# BatteryCharger.net
KiCad netlist of a schematic drawn in Altium Designer
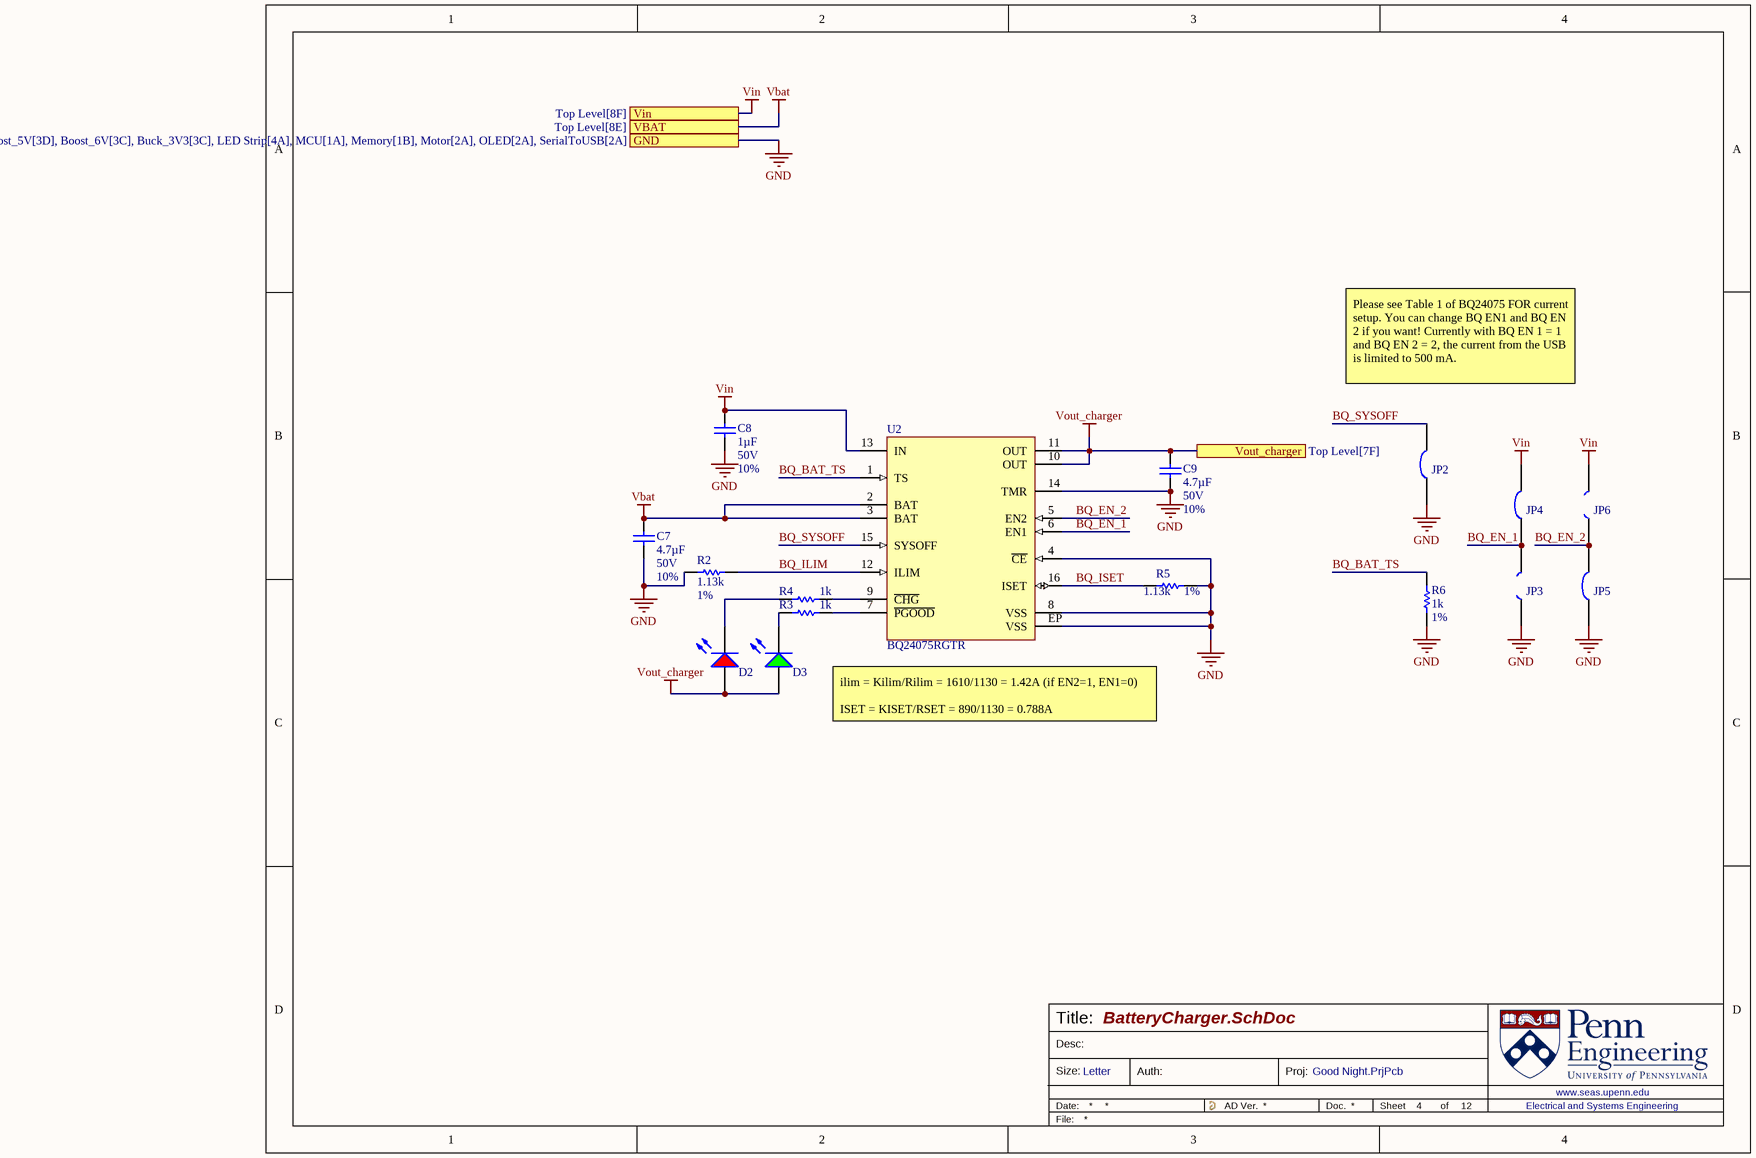
[diagram p0: BatteryCharger.SchDoc]

(export (version "E")
  (design (tool "Eeschema 10.0.6"))
  (components
    (comp (ref "C7")
      (value "4.7µF")
      (footprint "0805_CAP")
      (description "Capacitor Surface Mount 0805 Footprint 4.7UF 50V 10% Tolerance Ceramic X5R")
      (fields
        (field (name "VOLTAGE") "50V")
        (field (name "TOLERANCE") "10%")
        (field (name "Comment") "CAP 0805 4.7UF 50V 10% X5R")
      )
      (libsource (lib "University of Pennsylvania (ESE)") (part "cap"))
    )
    (comp (ref "C8")
      (value "1µF")
      (footprint "0603_CAP")
      (description "Capacitor Surface Mount 0603 Footprint 1UF 50V 10% Tolerance Ceramic X7R")
      (fields
        (field (name "VOLTAGE") "50V")
        (field (name "MANUFACTURER") "Various")
        (field (name "TOLERANCE") "10%")
        (field (name "Comment") "CAP 0603 1UF 50V 10% X7R")
      )
      (libsource (lib "University of Pennsylvania (ESE)") (part "cap"))
    )
    (comp (ref "C9")
      (value "4.7µF")
      (footprint "0805_CAP")
      (description "Capacitor Surface Mount 0805 Footprint 4.7UF 50V 10% Tolerance Ceramic X5R")
      (fields
        (field (name "VOLTAGE") "50V")
        (field (name "TOLERANCE") "10%")
        (field (name "Comment") "CAP 0805 4.7UF 50V 10% X5R")
      )
      (libsource (lib "University of Pennsylvania (ESE)") (part "cap"))
    )
    (comp (ref "D2")
      (value "LSM0805412V")
      (footprint "LED_0805_RED")
      (description "Single Color LED, RED, 0805")
      (libsource (lib "University of Pennsylvania (ESE)") (part "LED-RED-AK-2"))
    )
    (comp (ref "D3")
      (value "LSM0805452V")
      (footprint "LED_0805")
      (description "Single Color LED, Green, 0805")
      (libsource (lib "University of Pennsylvania (ESE)") (part "LED-GREEN-AK-2"))
    )
    (comp (ref "JP2")
      (value "0603 link")
      (footprint "0603_JP_RES")
      (description "0O link, SMD, 0603, Solder Bridge Option")
      (fields (field (name "MANUFACTURER") "Generic") (field (name "SOURCE") "Shunts and Jumpers.SchLib"))
      (libsource (lib "University of Pennsylvania (ESE)") (part "CMP-ROOT-0007-1"))
    )
    (comp (ref "JP3")
      (value "0603 link (Open)")
      (footprint "0603_JP_Open")
      (description "0O link, Solder Bridge/SMD, Open")
      (fields (field (name "SOURCE") "Shunts and Jumpers.SchLib"))
      (libsource (lib "University of Pennsylvania (ESE)") (part "CMP-ROOT-0012-1"))
    )
    (comp (ref "JP4")
      (value "0603 link")
      (footprint "0603_JP_RES")
      (description "0O link, SMD, 0603, Solder Bridge Option")
      (fields (field (name "MANUFACTURER") "Generic") (field (name "SOURCE") "Shunts and Jumpers.SchLib"))
      (libsource (lib "University of Pennsylvania (ESE)") (part "CMP-ROOT-0007-1"))
    )
    (comp (ref "JP5")
      (value "0603 link")
      (footprint "0603_JP_RES")
      (description "0O link, SMD, 0603, Solder Bridge Option")
      (fields (field (name "MANUFACTURER") "Generic") (field (name "SOURCE") "Shunts and Jumpers.SchLib"))
      (libsource (lib "") (part "CMP-ROOT-0007-1_1"))
    )
    (comp (ref "JP6")
      (value "0603 link (Open)")
      (footprint "0603_JP_Open")
      (description "0O link, Solder Bridge/SMD, Open")
      (fields (field (name "SOURCE") "Shunts and Jumpers.SchLib"))
      (libsource (lib "") (part "CMP-ROOT-0012-1_1"))
    )
    (comp (ref "R2")
      (value "1.13k")
      (footprint "0603_RES")
      (description "Resistor Surface Mount, 1.13K Ohms, 0603 Footprint, 1% Tolerance 0.1W")
      (fields
        (field (name "TOLERANCE") "1%")
        (field (name "MANUFACTURER") "Various")
        (field (name "Comment") "RES 0603 1.13K 1%")
      )
      (libsource (lib "University of Pennsylvania (ESE)") (part "res"))
    )
    (comp (ref "R3")
      (value "1k")
      (footprint "0603_RES")
      (description "Resistor Surface Mount, 1K Ohms, 0603 Footprint, 1% Tolerance 0.1W")
      (fields (field (name "JLCPCB PART #") "C21190") (field (name "MANUFACTURER") "Various"))
      (libsource (lib "University of Pennsylvania (ESE)") (part "res"))
    )
    (comp (ref "R4")
      (value "1k")
      (footprint "0603_RES")
      (description "Resistor Surface Mount, 1K Ohms, 0603 Footprint, 1% Tolerance 0.1W")
      (fields (field (name "JLCPCB PART #") "C21190") (field (name "MANUFACTURER") "Various"))
      (libsource (lib "University of Pennsylvania (ESE)") (part "res"))
    )
    (comp (ref "R5")
      (value "1.13k")
      (footprint "0603_RES")
      (description "Resistor Surface Mount, 1.13K Ohms, 0603 Footprint, 1% Tolerance 0.1W")
      (fields
        (field (name "TOLERANCE") "1%")
        (field (name "MANUFACTURER") "Various")
        (field (name "Comment") "RES 0603 1.13K 1%")
      )
      (libsource (lib "University of Pennsylvania (ESE)") (part "res"))
    )
    (comp (ref "R6")
      (value "1k")
      (footprint "0603_RES")
      (description "Resistor Surface Mount, 1K Ohms, 0603 Footprint, 1% Tolerance 0.1W")
      (fields
        (field (name "JLCPCB PART #") "C21190")
        (field (name "MANUFACTURER") "Various")
        (field (name "TOLERANCE") "1%")
      )
      (libsource (lib "University of Pennsylvania (ESE)") (part "res"))
    )
    (comp (ref "U2")
      (value "BQ24075RGTR")
      (footprint "FP-RGT0016C-IPC_A")
      (description "Power Supply Support Circuit, Adjustable, 1 Channel, 6.6, PQCC16")
      (libsource (lib "University of Pennsylvania (ESE)") (part "273aa663c5dc25a29e76a3da5be16cc"))
    )
  )
  (nets
    (net (code "1") (name "/BQ_BAT_TS") (class "Default")
      (node (ref "R6") (pin "2") (pinfunction "2_2") (pintype "passive"))
      (node (ref "U2") (pin "1") (pinfunction "TS_1") (pintype "input"))
    )
    (net (code "2") (name "/BQ_EN_1") (class "Default")
      (node (ref "JP3") (pin "2") (pinfunction "2_2") (pintype "passive"))
      (node (ref "JP4") (pin "1") (pinfunction "1_1") (pintype "passive"))
      (node (ref "U2") (pin "6") (pinfunction "EN1_6") (pintype "input"))
    )
    (net (code "3") (name "/BQ_EN_2") (class "Default")
      (node (ref "JP5") (pin "1") (pinfunction "1_1") (pintype "passive"))
      (node (ref "JP6") (pin "2") (pinfunction "2_2") (pintype "passive"))
      (node (ref "U2") (pin "5") (pinfunction "EN2_5") (pintype "input"))
    )
    (net (code "4") (name "/BQ_ILIM") (class "Default")
      (node (ref "R2") (pin "2") (pinfunction "2_2") (pintype "passive"))
      (node (ref "U2") (pin "12") (pinfunction "ILIM_12") (pintype "input"))
    )
    (net (code "5") (name "/BQ_ISET") (class "Default")
      (node (ref "R5") (pin "1") (pinfunction "1_1") (pintype "passive"))
      (node (ref "U2") (pin "16") (pinfunction "ISET_16") (pintype "bidirectional"))
    )
    (net (code "6") (name "/BQ_SYSOFF") (class "Default")
      (node (ref "JP2") (pin "2") (pinfunction "2_2") (pintype "passive"))
      (node (ref "U2") (pin "15") (pinfunction "SYSOFF_15") (pintype "input"))
    )
    (net (code "7") (name "GND") (class "Default")
      (node (ref "C7") (pin "1") (pinfunction "1_1") (pintype "passive"))
      (node (ref "C8") (pin "1") (pinfunction "1_1") (pintype "passive"))
      (node (ref "C9") (pin "1") (pinfunction "1_1") (pintype "passive"))
      (node (ref "JP2") (pin "1") (pinfunction "1_1") (pintype "passive"))
      (node (ref "JP3") (pin "1") (pinfunction "1_1") (pintype "passive"))
      (node (ref "JP5") (pin "2") (pinfunction "2_2") (pintype "passive"))
      (node (ref "R2") (pin "1") (pinfunction "1_1") (pintype "passive"))
      (node (ref "R5") (pin "2") (pinfunction "2_2") (pintype "passive"))
      (node (ref "R6") (pin "1") (pinfunction "1_1") (pintype "passive"))
      (node (ref "U2") (pin "14") (pinfunction "TMR_14") (pintype "passive"))
      (node (ref "U2") (pin "4") (pinfunction "~{CE}_4") (pintype "input"))
      (node (ref "U2") (pin "8") (pinfunction "VSS_8") (pintype "power_in"))
      (node (ref "U2") (pin "EP") (pinfunction "VSS_EP") (pintype "power_in"))
    )
    (net (code "8") (name "Net-(D2-PadK)") (class "Default")
      (node (ref "D2") (pin "K") (pinfunction "K_K") (pintype "passive"))
      (node (ref "R4") (pin "2") (pinfunction "2_2") (pintype "passive"))
    )
    (net (code "9") (name "Net-(D3-PadK)") (class "Default")
      (node (ref "D3") (pin "K") (pinfunction "K_K") (pintype "passive"))
      (node (ref "R3") (pin "2") (pinfunction "2_2") (pintype "passive"))
    )
    (net (code "10") (name "Net-(U2-~{CHG})") (class "Default")
      (node (ref "R4") (pin "1") (pinfunction "1_1") (pintype "passive"))
      (node (ref "U2") (pin "9") (pinfunction "~{CHG}_9") (pintype "tri_state"))
    )
    (net (code "11") (name "Net-(U2-~{PGOOD})") (class "Default")
      (node (ref "R3") (pin "1") (pinfunction "1_1") (pintype "passive"))
      (node (ref "U2") (pin "7") (pinfunction "~{PGOOD}_7") (pintype "tri_state"))
    )
    (net (code "12") (name "Vbat") (class "Default")
      (node (ref "C7") (pin "2") (pinfunction "2_2") (pintype "passive"))
      (node (ref "U2") (pin "2") (pinfunction "BAT_2") (pintype "power_in"))
      (node (ref "U2") (pin "3") (pinfunction "BAT_3") (pintype "power_in"))
    )
    (net (code "13") (name "Vin") (class "Default")
      (node (ref "C8") (pin "2") (pinfunction "2_2") (pintype "passive"))
      (node (ref "JP4") (pin "2") (pinfunction "2_2") (pintype "passive"))
      (node (ref "JP6") (pin "1") (pinfunction "1_1") (pintype "passive"))
      (node (ref "U2") (pin "13") (pinfunction "IN_13") (pintype "power_in"))
    )
    (net (code "14") (name "Vout_charger") (class "Default")
      (node (ref "C9") (pin "2") (pinfunction "2_2") (pintype "passive"))
      (node (ref "D2") (pin "A") (pinfunction "A_A") (pintype "passive"))
      (node (ref "D3") (pin "A") (pinfunction "A_A") (pintype "passive"))
      (node (ref "U2") (pin "10") (pinfunction "OUT_10") (pintype "power_in"))
      (node (ref "U2") (pin "11") (pinfunction "OUT_11") (pintype "power_in"))
    )
  )
)
